# Sens_HIH613x.net
KiCad netlist of a schematic drawn in EAGLE
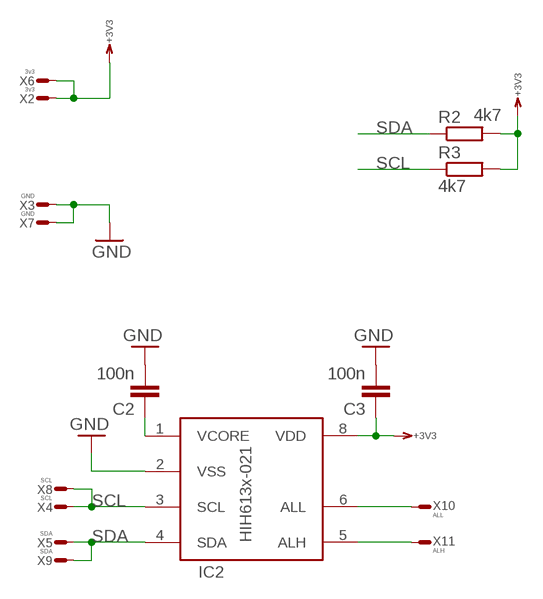
[diagram p0: schematic, sheet 1]

(export (version "E")
  (design (tool "Eeschema 10.0.6"))
  (components
    (comp (ref "C2")
      (value "100n")
      (footprint "eagle-import:0603")
      (libsource (lib "eagle-import") (part "C0603"))
    )
    (comp (ref "C3")
      (value "100n")
      (footprint "eagle-import:0603")
      (libsource (lib "eagle-import") (part "C0603"))
    )
    (comp (ref "IC2")
      (value "HIH613x-021")
      (footprint "eagle-import:SO8")
      (libsource (lib "eagle-import") (part "HIH613X"))
    )
    (comp (ref "R2")
      (value "4k7")
      (footprint "eagle-import:0603")
      (libsource (lib "eagle-import") (part "R0603"))
    )
    (comp (ref "R3")
      (value "4k7")
      (footprint "eagle-import:0603")
      (libsource (lib "eagle-import") (part "R0603"))
    )
    (comp (ref "X2")
      (value "3v3")
      (footprint "eagle-import:T1.6_0.9")
      (libsource (lib "eagle-import") (part "WIREPADT1.6/0.9"))
    )
    (comp (ref "X3")
      (value "GND")
      (footprint "eagle-import:T1.6_0.9")
      (libsource (lib "eagle-import") (part "WIREPADT1.6/0.9"))
    )
    (comp (ref "X4")
      (value "SCL")
      (footprint "eagle-import:T1.6_0.9")
      (libsource (lib "eagle-import") (part "WIREPADT1.6/0.9"))
    )
    (comp (ref "X5")
      (value "SDA")
      (footprint "eagle-import:T1.6_0.9")
      (libsource (lib "eagle-import") (part "WIREPADT1.6/0.9"))
    )
    (comp (ref "X6")
      (value "3v3")
      (footprint "eagle-import:T1.6_0.9")
      (libsource (lib "eagle-import") (part "WIREPADT1.6/0.9"))
    )
    (comp (ref "X7")
      (value "GND")
      (footprint "eagle-import:T1.6_0.9")
      (libsource (lib "eagle-import") (part "WIREPADT1.6/0.9"))
    )
    (comp (ref "X8")
      (value "SCL")
      (footprint "eagle-import:T1.6_0.9")
      (libsource (lib "eagle-import") (part "WIREPADT1.6/0.9"))
    )
    (comp (ref "X9")
      (value "SDA")
      (footprint "eagle-import:T1.6_0.9")
      (libsource (lib "eagle-import") (part "WIREPADT1.6/0.9"))
    )
    (comp (ref "X10")
      (value "ALL")
      (footprint "eagle-import:S1.27R")
      (libsource (lib "eagle-import") (part "WIREPADR"))
    )
    (comp (ref "X11")
      (value "ALH")
      (footprint "eagle-import:S1.27R")
      (libsource (lib "eagle-import") (part "WIREPADR"))
    )
  )
  (nets
    (net (code "1") (name "+3V3") (class "Default")
      (node (ref "C3") (pin "1") (pinfunction "1_1") (pintype "passive"))
      (node (ref "IC2") (pin "8") (pinfunction "VDD_8") (pintype "bidirectional"))
      (node (ref "R2") (pin "2") (pinfunction "2_2") (pintype "passive"))
      (node (ref "R3") (pin "2") (pinfunction "2_2") (pintype "passive"))
      (node (ref "X2") (pin "1") (pinfunction "S_1") (pintype "passive"))
      (node (ref "X6") (pin "1") (pinfunction "S_1") (pintype "passive"))
    )
    (net (code "2") (name "/SCL") (class "Default")
      (node (ref "IC2") (pin "3") (pinfunction "SCL_3") (pintype "bidirectional"))
      (node (ref "R3") (pin "1") (pinfunction "1_1") (pintype "passive"))
      (node (ref "X4") (pin "1") (pinfunction "S_1") (pintype "passive"))
      (node (ref "X8") (pin "1") (pinfunction "S_1") (pintype "passive"))
    )
    (net (code "3") (name "/SDA") (class "Default")
      (node (ref "IC2") (pin "4") (pinfunction "SDA_4") (pintype "bidirectional"))
      (node (ref "R2") (pin "1") (pinfunction "1_1") (pintype "passive"))
      (node (ref "X5") (pin "1") (pinfunction "S_1") (pintype "passive"))
      (node (ref "X9") (pin "1") (pinfunction "S_1") (pintype "passive"))
    )
    (net (code "4") (name "GND") (class "Default")
      (node (ref "C2") (pin "2") (pinfunction "2_2") (pintype "passive"))
      (node (ref "C3") (pin "2") (pinfunction "2_2") (pintype "passive"))
      (node (ref "IC2") (pin "2") (pinfunction "VSS_2") (pintype "bidirectional"))
      (node (ref "X3") (pin "1") (pinfunction "S_1") (pintype "passive"))
      (node (ref "X7") (pin "1") (pinfunction "S_1") (pintype "passive"))
    )
    (net (code "5") (name "Net-(IC2-ALH)") (class "Default")
      (node (ref "IC2") (pin "5") (pinfunction "ALH_5") (pintype "bidirectional"))
      (node (ref "X11") (pin "1") (pinfunction "S_1") (pintype "passive"))
    )
    (net (code "6") (name "Net-(IC2-ALL)") (class "Default")
      (node (ref "IC2") (pin "6") (pinfunction "ALL_6") (pintype "bidirectional"))
      (node (ref "X10") (pin "1") (pinfunction "S_1") (pintype "passive"))
    )
    (net (code "7") (name "Net-(IC2-VCORE)") (class "Default")
      (node (ref "C2") (pin "1") (pinfunction "1_1") (pintype "passive"))
      (node (ref "IC2") (pin "1") (pinfunction "VCORE_1") (pintype "bidirectional"))
    )
  )
)
